# Shiftregisters.net
KiCad netlist of a schematic drawn in Altium Designer
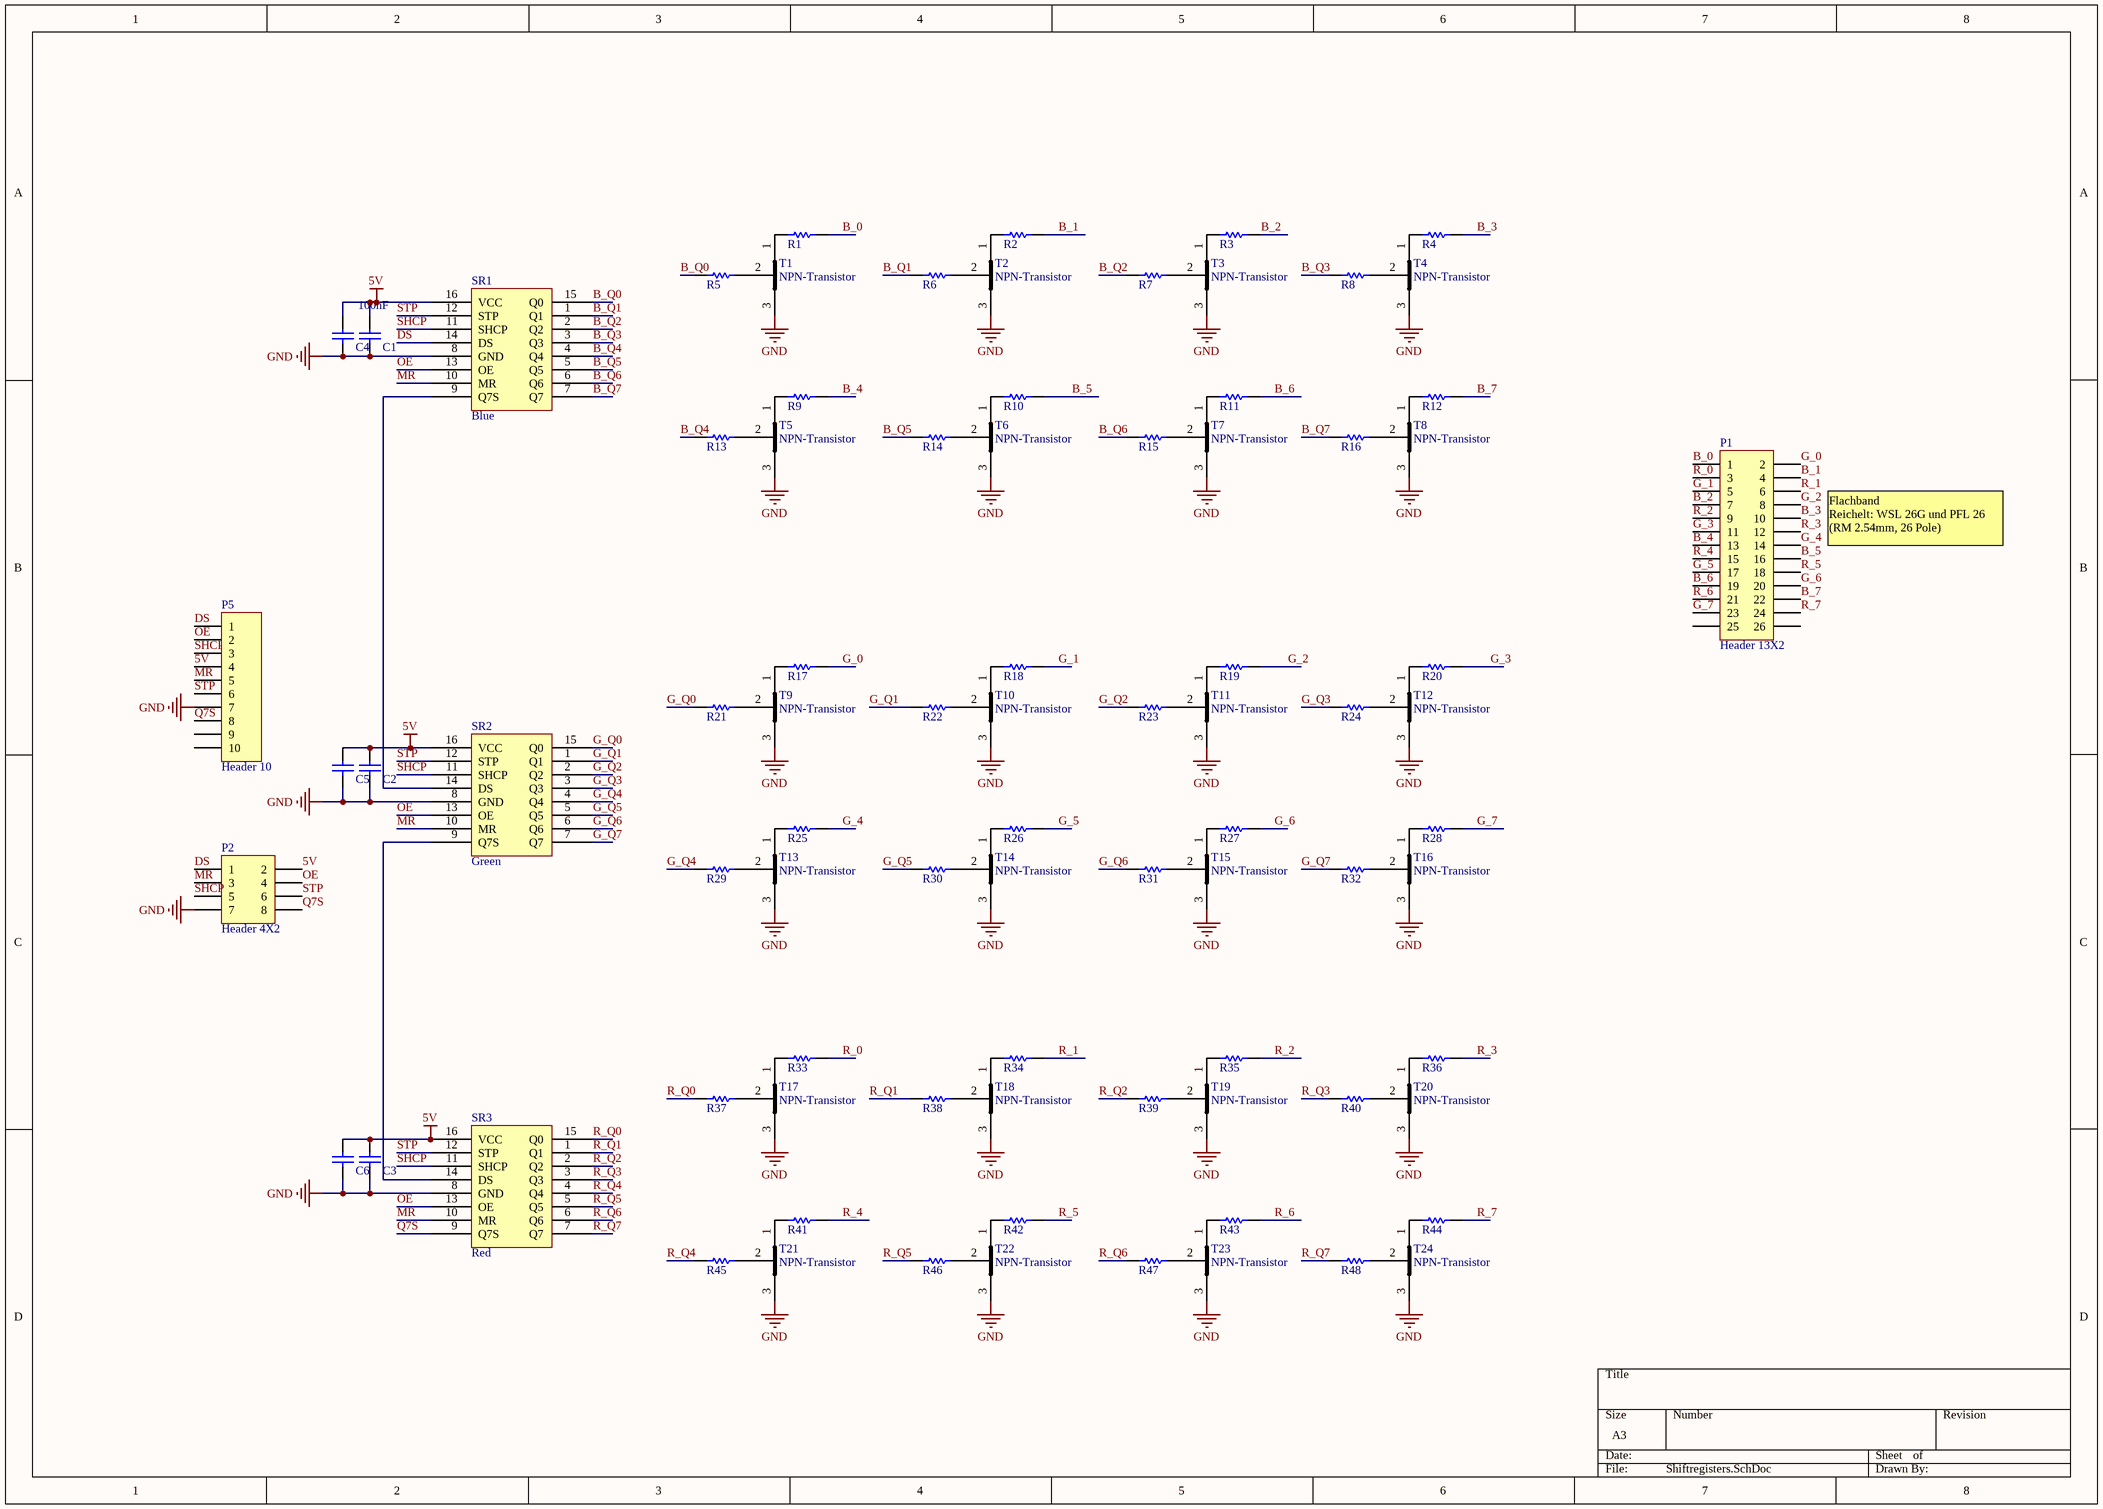
[diagram p0: Shiftregisters.SchDoc]

(export (version "E")
  (design (tool "Eeschema 10.0.6"))
  (components
    (comp (ref "C1")
      (value "100nF")
      (footprint "CAPC1206(3216)190_L")
      (description "CAP 100nF 16V Â±1% 1206 (3216 Metric) Thickness 1.9mm SMD")
      (fields (field (name "TOLERANCE") "Â±1%") (field (name "Comment") "CAP 100nF 16V 1206(3216)"))
      (libsource (lib "Altium Content Vault") (part "CMP-1037-04176-1"))
    )
    (comp (ref "C2")
      (value "CAP 100nF 16V 1206(3216)")
      (footprint "CAPC1206(3216)190_L")
      (description "CAP 100nF 16V Â±1% 1206 (3216 Metric) Thickness 1.9mm SMD")
      (fields (field (name "TOLERANCE") "Â±1%"))
      (libsource (lib "Altium Content Vault") (part "CAP"))
    )
    (comp (ref "C3")
      (value "CAP 100nF 16V 1206(3216)")
      (footprint "CAPC1206(3216)190_L")
      (description "CAP 100nF 16V Â±1% 1206 (3216 Metric) Thickness 1.9mm SMD")
      (fields (field (name "TOLERANCE") "Â±1%"))
      (libsource (lib "Altium Content Vault") (part "CAP"))
    )
    (comp (ref "C4")
      (value "CAP 1uF 16V 1206(3216)")
      (footprint "CAPC1206(3216)150_L")
      (description "CAP 1uF 16V Â±5% 1206 (3216 Metric) Thickness 1.45mm SMD")
      (fields (field (name "TOLERANCE") "Â±5%"))
      (libsource (lib "Altium Content Vault") (part "CAP"))
    )
    (comp (ref "C5")
      (value "CAP 1uF 16V 1206(3216)")
      (footprint "CAPC1206(3216)150_L")
      (description "CAP 1uF 16V Â±5% 1206 (3216 Metric) Thickness 1.45mm SMD")
      (fields (field (name "TOLERANCE") "Â±5%"))
      (libsource (lib "Altium Content Vault") (part "CAP"))
    )
    (comp (ref "C6")
      (value "CAP 1uF 16V 1206(3216)")
      (footprint "CAPC1206(3216)150_L")
      (description "CAP 1uF 16V Â±5% 1206 (3216 Metric) Thickness 1.45mm SMD")
      (fields (field (name "TOLERANCE") "Â±5%"))
      (libsource (lib "Altium Content Vault") (part "CAP"))
    )
    (comp (ref "P1")
      (value "Header 13X2")
      (footprint "HDR2X13")
      (description "Header, 13-Pin, Dual row")
      (fields (field (name "PUBLISHER") "Altium Limited"))
      (libsource (lib "Miscellaneous Connectors") (part "Header 13X2"))
    )
    (comp (ref "P2")
      (value "Header 4X2")
      (footprint "HDR2X4")
      (description "Header, 4-Pin, Dual row")
      (fields (field (name "PUBLISHER") "Altium Limited"))
      (libsource (lib "Miscellaneous Connectors") (part "Header 4X2"))
    )
    (comp (ref "P5")
      (value "Header 10")
      (footprint "10Pol Phoenix")
      (description "Header, 10-Pin")
      (fields (field (name "PUBLISHER") "Altium Limited"))
      (libsource (lib "Miscellaneous Connectors") (part "Header 10"))
    )
    (comp (ref "R1")
      (value "2R 5% 1206(3216)")
      (footprint "RESC1206(3216)_M")
      (description "2R 0.25W 5% 1206 (3216 Metric)  SMD")
      (fields (field (name "TOLERANCE") "5 %") (field (name "POWER") "0.25 W"))
      (libsource (lib "Altium Content Vault") (part "RES"))
    )
    (comp (ref "R2")
      (value "2R 5% 1206(3216)")
      (footprint "RESC1206(3216)_M")
      (description "2R 0.25W 5% 1206 (3216 Metric)  SMD")
      (fields (field (name "TOLERANCE") "5 %") (field (name "POWER") "0.25 W"))
      (libsource (lib "Altium Content Vault") (part "RES"))
    )
    (comp (ref "R3")
      (value "2R 5% 1206(3216)")
      (footprint "RESC1206(3216)_M")
      (description "2R 0.25W 5% 1206 (3216 Metric)  SMD")
      (fields (field (name "TOLERANCE") "5 %") (field (name "POWER") "0.25 W"))
      (libsource (lib "Altium Content Vault") (part "RES"))
    )
    (comp (ref "R4")
      (value "2R 5% 1206(3216)")
      (footprint "RESC1206(3216)_M")
      (description "2R 0.25W 5% 1206 (3216 Metric)  SMD")
      (fields (field (name "TOLERANCE") "5 %") (field (name "POWER") "0.25 W"))
      (libsource (lib "Altium Content Vault") (part "RES"))
    )
    (comp (ref "R5")
      (value "2R 5% 1206(3216)")
      (footprint "RESC1206(3216)_M")
      (description "2R 0.25W 5% 1206 (3216 Metric)  SMD")
      (fields (field (name "TOLERANCE") "5 %") (field (name "POWER") "0.25 W"))
      (libsource (lib "Altium Content Vault") (part "CMP-1014-00009-1"))
    )
    (comp (ref "R6")
      (value "2R 5% 1206(3216)")
      (footprint "RESC1206(3216)_M")
      (description "2R 0.25W 5% 1206 (3216 Metric)  SMD")
      (fields (field (name "TOLERANCE") "5 %") (field (name "POWER") "0.25 W"))
      (libsource (lib "Altium Content Vault") (part "RES"))
    )
    (comp (ref "R7")
      (value "2R 5% 1206(3216)")
      (footprint "RESC1206(3216)_M")
      (description "2R 0.25W 5% 1206 (3216 Metric)  SMD")
      (fields (field (name "TOLERANCE") "5 %") (field (name "POWER") "0.25 W"))
      (libsource (lib "Altium Content Vault") (part "RES"))
    )
    (comp (ref "R8")
      (value "2R 5% 1206(3216)")
      (footprint "RESC1206(3216)_M")
      (description "2R 0.25W 5% 1206 (3216 Metric)  SMD")
      (fields (field (name "TOLERANCE") "5 %") (field (name "POWER") "0.25 W"))
      (libsource (lib "Altium Content Vault") (part "RES"))
    )
    (comp (ref "R9")
      (value "2R 5% 1206(3216)")
      (footprint "RESC1206(3216)_M")
      (description "2R 0.25W 5% 1206 (3216 Metric)  SMD")
      (fields (field (name "TOLERANCE") "5 %") (field (name "POWER") "0.25 W"))
      (libsource (lib "Altium Content Vault") (part "RES"))
    )
    (comp (ref "R10")
      (value "2R 5% 1206(3216)")
      (footprint "RESC1206(3216)_M")
      (description "2R 0.25W 5% 1206 (3216 Metric)  SMD")
      (fields (field (name "TOLERANCE") "5 %") (field (name "POWER") "0.25 W"))
      (libsource (lib "Altium Content Vault") (part "RES"))
    )
    (comp (ref "R11")
      (value "2R 5% 1206(3216)")
      (footprint "RESC1206(3216)_M")
      (description "2R 0.25W 5% 1206 (3216 Metric)  SMD")
      (fields (field (name "TOLERANCE") "5 %") (field (name "POWER") "0.25 W"))
      (libsource (lib "Altium Content Vault") (part "RES"))
    )
    (comp (ref "R12")
      (value "2R 5% 1206(3216)")
      (footprint "RESC1206(3216)_M")
      (description "2R 0.25W 5% 1206 (3216 Metric)  SMD")
      (fields (field (name "TOLERANCE") "5 %") (field (name "POWER") "0.25 W"))
      (libsource (lib "Altium Content Vault") (part "RES"))
    )
    (comp (ref "R13")
      (value "2R 5% 1206(3216)")
      (footprint "RESC1206(3216)_M")
      (description "2R 0.25W 5% 1206 (3216 Metric)  SMD")
      (fields (field (name "TOLERANCE") "5 %") (field (name "POWER") "0.25 W"))
      (libsource (lib "Altium Content Vault") (part "RES"))
    )
    (comp (ref "R14")
      (value "2R 5% 1206(3216)")
      (footprint "RESC1206(3216)_M")
      (description "2R 0.25W 5% 1206 (3216 Metric)  SMD")
      (fields (field (name "TOLERANCE") "5 %") (field (name "POWER") "0.25 W"))
      (libsource (lib "Altium Content Vault") (part "RES"))
    )
    (comp (ref "R15")
      (value "2R 5% 1206(3216)")
      (footprint "RESC1206(3216)_M")
      (description "2R 0.25W 5% 1206 (3216 Metric)  SMD")
      (fields (field (name "TOLERANCE") "5 %") (field (name "POWER") "0.25 W"))
      (libsource (lib "Altium Content Vault") (part "RES"))
    )
    (comp (ref "R16")
      (value "2R 5% 1206(3216)")
      (footprint "RESC1206(3216)_M")
      (description "2R 0.25W 5% 1206 (3216 Metric)  SMD")
      (fields (field (name "TOLERANCE") "5 %") (field (name "POWER") "0.25 W"))
      (libsource (lib "Altium Content Vault") (part "RES"))
    )
    (comp (ref "R17")
      (value "2R 5% 1206(3216)")
      (footprint "RESC1206(3216)_M")
      (description "2R 0.25W 5% 1206 (3216 Metric)  SMD")
      (fields (field (name "TOLERANCE") "5 %") (field (name "POWER") "0.25 W"))
      (libsource (lib "Altium Content Vault") (part "RES"))
    )
    (comp (ref "R18")
      (value "2R 5% 1206(3216)")
      (footprint "RESC1206(3216)_M")
      (description "2R 0.25W 5% 1206 (3216 Metric)  SMD")
      (fields (field (name "TOLERANCE") "5 %") (field (name "POWER") "0.25 W"))
      (libsource (lib "Altium Content Vault") (part "RES"))
    )
    (comp (ref "R19")
      (value "2R 5% 1206(3216)")
      (footprint "RESC1206(3216)_M")
      (description "2R 0.25W 5% 1206 (3216 Metric)  SMD")
      (fields (field (name "TOLERANCE") "5 %") (field (name "POWER") "0.25 W"))
      (libsource (lib "Altium Content Vault") (part "RES"))
    )
    (comp (ref "R20")
      (value "2R 5% 1206(3216)")
      (footprint "RESC1206(3216)_M")
      (description "2R 0.25W 5% 1206 (3216 Metric)  SMD")
      (fields (field (name "TOLERANCE") "5 %") (field (name "POWER") "0.25 W"))
      (libsource (lib "Altium Content Vault") (part "RES"))
    )
    (comp (ref "R21")
      (value "2R 5% 1206(3216)")
      (footprint "RESC1206(3216)_M")
      (description "2R 0.25W 5% 1206 (3216 Metric)  SMD")
      (fields (field (name "TOLERANCE") "5 %") (field (name "POWER") "0.25 W"))
      (libsource (lib "Altium Content Vault") (part "RES"))
    )
    (comp (ref "R22")
      (value "2R 5% 1206(3216)")
      (footprint "RESC1206(3216)_M")
      (description "2R 0.25W 5% 1206 (3216 Metric)  SMD")
      (fields (field (name "TOLERANCE") "5 %") (field (name "POWER") "0.25 W"))
      (libsource (lib "Altium Content Vault") (part "RES"))
    )
    (comp (ref "R23")
      (value "2R 5% 1206(3216)")
      (footprint "RESC1206(3216)_M")
      (description "2R 0.25W 5% 1206 (3216 Metric)  SMD")
      (fields (field (name "TOLERANCE") "5 %") (field (name "POWER") "0.25 W"))
      (libsource (lib "Altium Content Vault") (part "RES"))
    )
    (comp (ref "R24")
      (value "2R 5% 1206(3216)")
      (footprint "RESC1206(3216)_M")
      (description "2R 0.25W 5% 1206 (3216 Metric)  SMD")
      (fields (field (name "TOLERANCE") "5 %") (field (name "POWER") "0.25 W"))
      (libsource (lib "Altium Content Vault") (part "RES"))
    )
    (comp (ref "R25")
      (value "2R 5% 1206(3216)")
      (footprint "RESC1206(3216)_M")
      (description "2R 0.25W 5% 1206 (3216 Metric)  SMD")
      (fields (field (name "TOLERANCE") "5 %") (field (name "POWER") "0.25 W"))
      (libsource (lib "Altium Content Vault") (part "RES"))
    )
    (comp (ref "R26")
      (value "2R 5% 1206(3216)")
      (footprint "RESC1206(3216)_M")
      (description "2R 0.25W 5% 1206 (3216 Metric)  SMD")
      (fields (field (name "TOLERANCE") "5 %") (field (name "POWER") "0.25 W"))
      (libsource (lib "Altium Content Vault") (part "RES"))
    )
    (comp (ref "R27")
      (value "2R 5% 1206(3216)")
      (footprint "RESC1206(3216)_M")
      (description "2R 0.25W 5% 1206 (3216 Metric)  SMD")
      (fields (field (name "TOLERANCE") "5 %") (field (name "POWER") "0.25 W"))
      (libsource (lib "Altium Content Vault") (part "RES"))
    )
    (comp (ref "R28")
      (value "2R 5% 1206(3216)")
      (footprint "RESC1206(3216)_M")
      (description "2R 0.25W 5% 1206 (3216 Metric)  SMD")
      (fields (field (name "TOLERANCE") "5 %") (field (name "POWER") "0.25 W"))
      (libsource (lib "Altium Content Vault") (part "RES"))
    )
    (comp (ref "R29")
      (value "2R 5% 1206(3216)")
      (footprint "RESC1206(3216)_M")
      (description "2R 0.25W 5% 1206 (3216 Metric)  SMD")
      (fields (field (name "TOLERANCE") "5 %") (field (name "POWER") "0.25 W"))
      (libsource (lib "Altium Content Vault") (part "RES"))
    )
    (comp (ref "R30")
      (value "2R 5% 1206(3216)")
      (footprint "RESC1206(3216)_M")
      (description "2R 0.25W 5% 1206 (3216 Metric)  SMD")
      (fields (field (name "TOLERANCE") "5 %") (field (name "POWER") "0.25 W"))
      (libsource (lib "Altium Content Vault") (part "RES"))
    )
    (comp (ref "R31")
      (value "2R 5% 1206(3216)")
      (footprint "RESC1206(3216)_M")
      (description "2R 0.25W 5% 1206 (3216 Metric)  SMD")
      (fields (field (name "TOLERANCE") "5 %") (field (name "POWER") "0.25 W"))
      (libsource (lib "Altium Content Vault") (part "RES"))
    )
    (comp (ref "R32")
      (value "2R 5% 1206(3216)")
      (footprint "RESC1206(3216)_M")
      (description "2R 0.25W 5% 1206 (3216 Metric)  SMD")
      (fields (field (name "TOLERANCE") "5 %") (field (name "POWER") "0.25 W"))
      (libsource (lib "Altium Content Vault") (part "RES"))
    )
    (comp (ref "R33")
      (value "2R 5% 1206(3216)")
      (footprint "RESC1206(3216)_M")
      (description "2R 0.25W 5% 1206 (3216 Metric)  SMD")
      (fields (field (name "TOLERANCE") "5 %") (field (name "POWER") "0.25 W"))
      (libsource (lib "Altium Content Vault") (part "RES"))
    )
    (comp (ref "R34")
      (value "2R 5% 1206(3216)")
      (footprint "RESC1206(3216)_M")
      (description "2R 0.25W 5% 1206 (3216 Metric)  SMD")
      (fields (field (name "TOLERANCE") "5 %") (field (name "POWER") "0.25 W"))
      (libsource (lib "Altium Content Vault") (part "RES"))
    )
    (comp (ref "R35")
      (value "2R 5% 1206(3216)")
      (footprint "RESC1206(3216)_M")
      (description "2R 0.25W 5% 1206 (3216 Metric)  SMD")
      (fields (field (name "TOLERANCE") "5 %") (field (name "POWER") "0.25 W"))
      (libsource (lib "Altium Content Vault") (part "RES"))
    )
    (comp (ref "R36")
      (value "2R 5% 1206(3216)")
      (footprint "RESC1206(3216)_M")
      (description "2R 0.25W 5% 1206 (3216 Metric)  SMD")
      (fields (field (name "TOLERANCE") "5 %") (field (name "POWER") "0.25 W"))
      (libsource (lib "Altium Content Vault") (part "RES"))
    )
    (comp (ref "R37")
      (value "2R 5% 1206(3216)")
      (footprint "RESC1206(3216)_M")
      (description "2R 0.25W 5% 1206 (3216 Metric)  SMD")
      (fields (field (name "TOLERANCE") "5 %") (field (name "POWER") "0.25 W"))
      (libsource (lib "Altium Content Vault") (part "RES"))
    )
    (comp (ref "R38")
      (value "2R 5% 1206(3216)")
      (footprint "RESC1206(3216)_M")
      (description "2R 0.25W 5% 1206 (3216 Metric)  SMD")
      (fields (field (name "TOLERANCE") "5 %") (field (name "POWER") "0.25 W"))
      (libsource (lib "Altium Content Vault") (part "RES"))
    )
    (comp (ref "R39")
      (value "2R 5% 1206(3216)")
      (footprint "RESC1206(3216)_M")
      (description "2R 0.25W 5% 1206 (3216 Metric)  SMD")
      (fields (field (name "TOLERANCE") "5 %") (field (name "POWER") "0.25 W"))
      (libsource (lib "Altium Content Vault") (part "RES"))
    )
    (comp (ref "R40")
      (value "2R 5% 1206(3216)")
      (footprint "RESC1206(3216)_M")
      (description "2R 0.25W 5% 1206 (3216 Metric)  SMD")
      (fields (field (name "TOLERANCE") "5 %") (field (name "POWER") "0.25 W"))
      (libsource (lib "Altium Content Vault") (part "RES"))
    )
    (comp (ref "R41")
      (value "2R 5% 1206(3216)")
      (footprint "RESC1206(3216)_M")
      (description "2R 0.25W 5% 1206 (3216 Metric)  SMD")
      (fields (field (name "TOLERANCE") "5 %") (field (name "POWER") "0.25 W"))
      (libsource (lib "Altium Content Vault") (part "RES"))
    )
    (comp (ref "R42")
      (value "2R 5% 1206(3216)")
      (footprint "RESC1206(3216)_M")
      (description "2R 0.25W 5% 1206 (3216 Metric)  SMD")
      (fields (field (name "TOLERANCE") "5 %") (field (name "POWER") "0.25 W"))
      (libsource (lib "Altium Content Vault") (part "RES"))
    )
    (comp (ref "R43")
      (value "2R 5% 1206(3216)")
      (footprint "RESC1206(3216)_M")
      (description "2R 0.25W 5% 1206 (3216 Metric)  SMD")
      (fields (field (name "TOLERANCE") "5 %") (field (name "POWER") "0.25 W"))
      (libsource (lib "Altium Content Vault") (part "RES"))
    )
    (comp (ref "R44")
      (value "2R 5% 1206(3216)")
      (footprint "RESC1206(3216)_M")
      (description "2R 0.25W 5% 1206 (3216 Metric)  SMD")
      (fields (field (name "TOLERANCE") "5 %") (field (name "POWER") "0.25 W"))
      (libsource (lib "Altium Content Vault") (part "RES"))
    )
    (comp (ref "R45")
      (value "2R 5% 1206(3216)")
      (footprint "RESC1206(3216)_M")
      (description "2R 0.25W 5% 1206 (3216 Metric)  SMD")
      (fields (field (name "TOLERANCE") "5 %") (field (name "POWER") "0.25 W"))
      (libsource (lib "Altium Content Vault") (part "CMP-1014-00009-1"))
    )
    (comp (ref "R46")
      (value "2R 5% 1206(3216)")
      (footprint "RESC1206(3216)_M")
      (description "2R 0.25W 5% 1206 (3216 Metric)  SMD")
      (fields (field (name "TOLERANCE") "5 %") (field (name "POWER") "0.25 W"))
      (libsource (lib "Altium Content Vault") (part "RES"))
    )
    (comp (ref "R47")
      (value "2R 5% 1206(3216)")
      (footprint "RESC1206(3216)_M")
      (description "2R 0.25W 5% 1206 (3216 Metric)  SMD")
      (fields (field (name "TOLERANCE") "5 %") (field (name "POWER") "0.25 W"))
      (libsource (lib "Altium Content Vault") (part "RES"))
    )
    (comp (ref "R48")
      (value "2R 5% 1206(3216)")
      (footprint "RESC1206(3216)_M")
      (description "2R 0.25W 5% 1206 (3216 Metric)  SMD")
      (fields (field (name "TOLERANCE") "5 %") (field (name "POWER") "0.25 W"))
      (libsource (lib "Altium Content Vault") (part "RES"))
    )
    (comp (ref "SR1")
      (value "Blue")
      (footprint "SOP16")
      (description "74HC595 Farnell:  2098004")
      (libsource (lib "RGB-Cube") (part "74HC595"))
    )
    (comp (ref "SR2")
      (value "Green")
      (footprint "SOP16")
      (description "74HC595 Farnell:  2098004")
      (libsource (lib "RGB-Cube") (part "74HC595"))
    )
    (comp (ref "SR3")
      (value "Red")
      (footprint "SOP16")
      (description "74HC595 Farnell:  2098004")
      (libsource (lib "RGB-Cube") (part "74HC595"))
    )
    (comp (ref "T1")
      (value "NPN-Transistor")
      (footprint "2N3904 - duplicate")
      (libsource (lib "RGB-Cube") (part "NPN-Transistor"))
    )
    (comp (ref "T2")
      (value "NPN-Transistor")
      (footprint "2N3904 - duplicate")
      (libsource (lib "RGB-Cube") (part "NPN-Transistor"))
    )
    (comp (ref "T3")
      (value "NPN-Transistor")
      (footprint "2N3904 - duplicate")
      (libsource (lib "RGB-Cube") (part "NPN-Transistor"))
    )
    (comp (ref "T4")
      (value "NPN-Transistor")
      (footprint "2N3904 - duplicate")
      (libsource (lib "RGB-Cube") (part "NPN-Transistor"))
    )
    (comp (ref "T5")
      (value "NPN-Transistor")
      (footprint "2N3904 - duplicate")
      (libsource (lib "RGB-Cube") (part "NPN-Transistor"))
    )
    (comp (ref "T6")
      (value "NPN-Transistor")
      (footprint "2N3904 - duplicate")
      (libsource (lib "RGB-Cube") (part "NPN-Transistor"))
    )
    (comp (ref "T7")
      (value "NPN-Transistor")
      (footprint "2N3904 - duplicate")
      (libsource (lib "RGB-Cube") (part "NPN-Transistor"))
    )
    (comp (ref "T8")
      (value "NPN-Transistor")
      (footprint "2N3904 - duplicate")
      (libsource (lib "RGB-Cube") (part "NPN-Transistor"))
    )
    (comp (ref "T9")
      (value "NPN-Transistor")
      (footprint "2N3904 - duplicate")
      (libsource (lib "RGB-Cube") (part "NPN-Transistor"))
    )
    (comp (ref "T10")
      (value "NPN-Transistor")
      (footprint "2N3904 - duplicate")
      (libsource (lib "RGB-Cube") (part "NPN-Transistor"))
    )
    (comp (ref "T11")
      (value "NPN-Transistor")
      (footprint "2N3904 - duplicate")
      (libsource (lib "RGB-Cube") (part "NPN-Transistor"))
    )
    (comp (ref "T12")
      (value "NPN-Transistor")
      (footprint "2N3904 - duplicate")
      (libsource (lib "RGB-Cube") (part "NPN-Transistor"))
    )
    (comp (ref "T13")
      (value "NPN-Transistor")
      (footprint "2N3904 - duplicate")
      (libsource (lib "RGB-Cube") (part "NPN-Transistor"))
    )
    (comp (ref "T14")
      (value "NPN-Transistor")
      (footprint "2N3904 - duplicate")
      (libsource (lib "RGB-Cube") (part "NPN-Transistor"))
    )
    (comp (ref "T15")
      (value "NPN-Transistor")
      (footprint "2N3904 - duplicate")
      (libsource (lib "RGB-Cube") (part "NPN-Transistor"))
    )
    (comp (ref "T16")
      (value "NPN-Transistor")
      (footprint "2N3904 - duplicate")
      (libsource (lib "RGB-Cube") (part "NPN-Transistor"))
    )
    (comp (ref "T17")
      (value "NPN-Transistor")
      (footprint "2N3904 - duplicate")
      (libsource (lib "RGB-Cube") (part "NPN-Transistor"))
    )
    (comp (ref "T18")
      (value "NPN-Transistor")
      (footprint "2N3904 - duplicate")
      (libsource (lib "RGB-Cube") (part "NPN-Transistor"))
    )
    (comp (ref "T19")
      (value "NPN-Transistor")
      (footprint "2N3904 - duplicate")
      (libsource (lib "RGB-Cube") (part "NPN-Transistor"))
    )
    (comp (ref "T20")
      (value "NPN-Transistor")
      (footprint "2N3904 - duplicate")
      (libsource (lib "RGB-Cube") (part "NPN-Transistor"))
    )
    (comp (ref "T21")
      (value "NPN-Transistor")
      (footprint "2N3904 - duplicate")
      (libsource (lib "RGB-Cube") (part "NPN-Transistor"))
    )
    (comp (ref "T22")
      (value "NPN-Transistor")
      (footprint "2N3904 - duplicate")
      (libsource (lib "RGB-Cube") (part "NPN-Transistor"))
    )
    (comp (ref "T23")
      (value "NPN-Transistor")
      (footprint "2N3904 - duplicate")
      (libsource (lib "RGB-Cube") (part "NPN-Transistor"))
    )
    (comp (ref "T24")
      (value "NPN-Transistor")
      (footprint "2N3904 - duplicate")
      (libsource (lib "RGB-Cube") (part "NPN-Transistor"))
    )
  )
  (nets
    (net (code "1") (name "/B_0") (class "Default")
      (node (ref "P1") (pin "1") (pinfunction "1_1") (pintype "passive"))
      (node (ref "R1") (pin "1") (pinfunction "1_1") (pintype "passive"))
    )
    (net (code "2") (name "/B_1") (class "Default")
      (node (ref "P1") (pin "4") (pinfunction "4_4") (pintype "passive"))
      (node (ref "R2") (pin "1") (pinfunction "1_1") (pintype "passive"))
    )
    (net (code "3") (name "/B_2") (class "Default")
      (node (ref "P1") (pin "7") (pinfunction "7_7") (pintype "passive"))
      (node (ref "R3") (pin "1") (pinfunction "1_1") (pintype "passive"))
    )
    (net (code "4") (name "/B_3") (class "Default")
      (node (ref "P1") (pin "10") (pinfunction "10_10") (pintype "passive"))
      (node (ref "R4") (pin "1") (pinfunction "1_1") (pintype "passive"))
    )
    (net (code "5") (name "/B_4") (class "Default")
      (node (ref "P1") (pin "13") (pinfunction "13_13") (pintype "passive"))
      (node (ref "R9") (pin "1") (pinfunction "1_1") (pintype "passive"))
    )
    (net (code "6") (name "/B_5") (class "Default")
      (node (ref "P1") (pin "16") (pinfunction "16_16") (pintype "passive"))
      (node (ref "R10") (pin "1") (pinfunction "1_1") (pintype "passive"))
    )
    (net (code "7") (name "/B_6") (class "Default")
      (node (ref "P1") (pin "19") (pinfunction "19_19") (pintype "passive"))
      (node (ref "R11") (pin "1") (pinfunction "1_1") (pintype "passive"))
    )
    (net (code "8") (name "/B_7") (class "Default")
      (node (ref "P1") (pin "22") (pinfunction "22_22") (pintype "passive"))
      (node (ref "R12") (pin "1") (pinfunction "1_1") (pintype "passive"))
    )
    (net (code "9") (name "/B_Q0") (class "Default")
      (node (ref "R5") (pin "1") (pinfunction "1_1") (pintype "passive"))
      (node (ref "SR1") (pin "15") (pinfunction "Q0_15") (pintype "passive"))
    )
    (net (code "10") (name "/B_Q1") (class "Default")
      (node (ref "R6") (pin "1") (pinfunction "1_1") (pintype "passive"))
      (node (ref "SR1") (pin "1") (pinfunction "Q1_1") (pintype "passive"))
    )
    (net (code "11") (name "/B_Q2") (class "Default")
      (node (ref "R7") (pin "1") (pinfunction "1_1") (pintype "passive"))
      (node (ref "SR1") (pin "2") (pinfunction "Q2_2") (pintype "passive"))
    )
    (net (code "12") (name "/B_Q3") (class "Default")
      (node (ref "R8") (pin "1") (pinfunction "1_1") (pintype "passive"))
      (node (ref "SR1") (pin "3") (pinfunction "Q3_3") (pintype "passive"))
    )
    (net (code "13") (name "/B_Q4") (class "Default")
      (node (ref "R13") (pin "1") (pinfunction "1_1") (pintype "passive"))
      (node (ref "SR1") (pin "4") (pinfunction "Q4_4") (pintype "passive"))
    )
    (net (code "14") (name "/B_Q5") (class "Default")
      (node (ref "R14") (pin "1") (pinfunction "1_1") (pintype "passive"))
      (node (ref "SR1") (pin "5") (pinfunction "Q5_5") (pintype "passive"))
    )
    (net (code "15") (name "/B_Q6") (class "Default")
      (node (ref "R15") (pin "1") (pinfunction "1_1") (pintype "passive"))
      (node (ref "SR1") (pin "6") (pinfunction "Q6_6") (pintype "passive"))
    )
    (net (code "16") (name "/B_Q7") (class "Default")
      (node (ref "R16") (pin "1") (pinfunction "1_1") (pintype "passive"))
      (node (ref "SR1") (pin "7") (pinfunction "Q7_7") (pintype "passive"))
    )
    (net (code "17") (name "/DS") (class "Default")
      (node (ref "P2") (pin "1") (pinfunction "1_1") (pintype "passive"))
      (node (ref "P5") (pin "1") (pinfunction "1_1") (pintype "passive"))
      (node (ref "SR1") (pin "14") (pinfunction "DS_14") (pintype "passive"))
    )
    (net (code "18") (name "/G_0") (class "Default")
      (node (ref "P1") (pin "2") (pinfunction "2_2") (pintype "passive"))
      (node (ref "R17") (pin "1") (pinfunction "1_1") (pintype "passive"))
    )
    (net (code "19") (name "/G_1") (class "Default")
      (node (ref "P1") (pin "5") (pinfunction "5_5") (pintype "passive"))
      (node (ref "R18") (pin "1") (pinfunction "1_1") (pintype "passive"))
    )
    (net (code "20") (name "/G_2") (class "Default")
      (node (ref "P1") (pin "8") (pinfunction "8_8") (pintype "passive"))
      (node (ref "R19") (pin "1") (pinfunction "1_1") (pintype "passive"))
    )
    (net (code "21") (name "/G_3") (class "Default")
      (node (ref "P1") (pin "11") (pinfunction "11_11") (pintype "passive"))
      (node (ref "R20") (pin "1") (pinfunction "1_1") (pintype "passive"))
    )
    (net (code "22") (name "/G_4") (class "Default")
      (node (ref "P1") (pin "14") (pinfunction "14_14") (pintype "passive"))
      (node (ref "R25") (pin "1") (pinfunction "1_1") (pintype "passive"))
    )
    (net (code "23") (name "/G_5") (class "Default")
      (node (ref "P1") (pin "17") (pinfunction "17_17") (pintype "passive"))
      (node (ref "R26") (pin "1") (pinfunction "1_1") (pintype "passive"))
    )
    (net (code "24") (name "/G_6") (class "Default")
      (node (ref "P1") (pin "20") (pinfunction "20_20") (pintype "passive"))
      (node (ref "R27") (pin "1") (pinfunction "1_1") (pintype "passive"))
    )
    (net (code "25") (name "/G_7") (class "Default")
      (node (ref "P1") (pin "23") (pinfunction "23_23") (pintype "passive"))
      (node (ref "R28") (pin "1") (pinfunction "1_1") (pintype "passive"))
    )
    (net (code "26") (name "/G_Q0") (class "Default")
      (node (ref "R21") (pin "1") (pinfunction "1_1") (pintype "passive"))
      (node (ref "SR2") (pin "15") (pinfunction "Q0_15") (pintype "passive"))
    )
    (net (code "27") (name "/G_Q1") (class "Default")
      (node (ref "R22") (pin "1") (pinfunction "1_1") (pintype "passive"))
      (node (ref "SR2") (pin "1") (pinfunction "Q1_1") (pintype "passive"))
    )
    (net (code "28") (name "/G_Q2") (class "Default")
      (node (ref "R23") (pin "1") (pinfunction "1_1") (pintype "passive"))
      (node (ref "SR2") (pin "2") (pinfunction "Q2_2") (pintype "passive"))
    )
    (net (code "29") (name "/G_Q3") (class "Default")
      (node (ref "R24") (pin "1") (pinfunction "1_1") (pintype "passive"))
      (node (ref "SR2") (pin "3") (pinfunction "Q3_3") (pintype "passive"))
    )
    (net (code "30") (name "/G_Q4") (class "Default")
      (node (ref "R29") (pin "1") (pinfunction "1_1") (pintype "passive"))
      (node (ref "SR2") (pin "4") (pinfunction "Q4_4") (pintype "passive"))
    )
    (net (code "31") (name "/G_Q5") (class "Default")
      (node (ref "R30") (pin "1") (pinfunction "1_1") (pintype "passive"))
      (node (ref "SR2") (pin "5") (pinfunction "Q5_5") (pintype "passive"))
    )
    (net (code "32") (name "/G_Q6") (class "Default")
      (node (ref "R31") (pin "1") (pinfunction "1_1") (pintype "passive"))
      (node (ref "SR2") (pin "6") (pinfunction "Q6_6") (pintype "passive"))
    )
    (net (code "33") (name "/G_Q7") (class "Default")
      (node (ref "R32") (pin "1") (pinfunction "1_1") (pintype "passive"))
      (node (ref "SR2") (pin "7") (pinfunction "Q7_7") (pintype "passive"))
    )
    (net (code "34") (name "/MR") (class "Default")
      (node (ref "P2") (pin "3") (pinfunction "3_3") (pintype "passive"))
      (node (ref "P5") (pin "5") (pinfunction "5_5") (pintype "passive"))
      (node (ref "SR1") (pin "10") (pinfunction "MR_10") (pintype "passive"))
      (node (ref "SR2") (pin "10") (pinfunction "MR_10") (pintype "passive"))
      (node (ref "SR3") (pin "10") (pinfunction "MR_10") (pintype "passive"))
    )
    (net (code "35") (name "/OE") (class "Default")
      (node (ref "P2") (pin "4") (pinfunction "4_4") (pintype "passive"))
      (node (ref "P5") (pin "2") (pinfunction "2_2") (pintype "passive"))
      (node (ref "SR1") (pin "13") (pinfunction "OE_13") (pintype "passive"))
      (node (ref "SR2") (pin "13") (pinfunction "OE_13") (pintype "passive"))
      (node (ref "SR3") (pin "13") (pinfunction "OE_13") (pintype "passive"))
    )
    (net (code "36") (name "/Q7S") (class "Default")
      (node (ref "P2") (pin "8") (pinfunction "8_8") (pintype "passive"))
      (node (ref "P5") (pin "8") (pinfunction "8_8") (pintype "passive"))
      (node (ref "SR3") (pin "9") (pinfunction "Q7S_9") (pintype "passive"))
    )
    (net (code "37") (name "/R_0") (class "Default")
      (node (ref "P1") (pin "3") (pinfunction "3_3") (pintype "passive"))
      (node (ref "R33") (pin "1") (pinfunction "1_1") (pintype "passive"))
    )
    (net (code "38") (name "/R_1") (class "Default")
      (node (ref "P1") (pin "6") (pinfunction "6_6") (pintype "passive"))
      (node (ref "R34") (pin "1") (pinfunction "1_1") (pintype "passive"))
    )
    (net (code "39") (name "/R_2") (class "Default")
      (node (ref "P1") (pin "9") (pinfunction "9_9") (pintype "passive"))
      (node (ref "R35") (pin "1") (pinfunction "1_1") (pintype "passive"))
    )
    (net (code "40") (name "/R_3") (class "Default")
      (node (ref "P1") (pin "12") (pinfunction "12_12") (pintype "passive"))
      (node (ref "R36") (pin "1") (pinfunction "1_1") (pintype "passive"))
    )
    (net (code "41") (name "/R_4") (class "Default")
      (node (ref "P1") (pin "15") (pinfunction "15_15") (pintype "passive"))
      (node (ref "R41") (pin "1") (pinfunction "1_1") (pintype "passive"))
    )
    (net (code "42") (name "/R_5") (class "Default")
      (node (ref "P1") (pin "18") (pinfunction "18_18") (pintype "passive"))
      (node (ref "R42") (pin "1") (pinfunction "1_1") (pintype "passive"))
    )
    (net (code "43") (name "/R_6") (class "Default")
      (node (ref "P1") (pin "21") (pinfunction "21_21") (pintype "passive"))
      (node (ref "R43") (pin "1") (pinfunction "1_1") (pintype "passive"))
    )
    (net (code "44") (name "/R_7") (class "Default")
      (node (ref "P1") (pin "24") (pinfunction "24_24") (pintype "passive"))
      (node (ref "R44") (pin "1") (pinfunction "1_1") (pintype "passive"))
    )
    (net (code "45") (name "/R_Q0") (class "Default")
      (node (ref "R37") (pin "1") (pinfunction "1_1") (pintype "passive"))
      (node (ref "SR3") (pin "15") (pinfunction "Q0_15") (pintype "passive"))
    )
    (net (code "46") (name "/R_Q1") (class "Default")
      (node (ref "R38") (pin "1") (pinfunction "1_1") (pintype "passive"))
      (node (ref "SR3") (pin "1") (pinfunction "Q1_1") (pintype "passive"))
    )
    (net (code "47") (name "/R_Q2") (class "Default")
      (node (ref "R39") (pin "1") (pinfunction "1_1") (pintype "passive"))
      (node (ref "SR3") (pin "2") (pinfunction "Q2_2") (pintype "passive"))
    )
    (net (code "48") (name "/R_Q3") (class "Default")
      (node (ref "R40") (pin "1") (pinfunction "1_1") (pintype "passive"))
      (node (ref "SR3") (pin "3") (pinfunction "Q3_3") (pintype "passive"))
    )
    (net (code "49") (name "/R_Q4") (class "Default")
      (node (ref "R45") (pin "1") (pinfunction "1_1") (pintype "passive"))
      (node (ref "SR3") (pin "4") (pinfunction "Q4_4") (pintype "passive"))
    )
    (net (code "50") (name "/R_Q5") (class "Default")
      (node (ref "R46") (pin "1") (pinfunction "1_1") (pintype "passive"))
      (node (ref "SR3") (pin "5") (pinfunction "Q5_5") (pintype "passive"))
    )
    (net (code "51") (name "/R_Q6") (class "Default")
      (node (ref "R47") (pin "1") (pinfunction "1_1") (pintype "passive"))
      (node (ref "SR3") (pin "6") (pinfunction "Q6_6") (pintype "passive"))
    )
    (net (code "52") (name "/R_Q7") (class "Default")
      (node (ref "R48") (pin "1") (pinfunction "1_1") (pintype "passive"))
      (node (ref "SR3") (pin "7") (pinfunction "Q7_7") (pintype "passive"))
    )
    (net (code "53") (name "/SHCP") (class "Default")
      (node (ref "P2") (pin "5") (pinfunction "5_5") (pintype "passive"))
      (node (ref "P5") (pin "3") (pinfunction "3_3") (pintype "passive"))
      (node (ref "SR1") (pin "11") (pinfunction "SHCP_11") (pintype "passive"))
      (node (ref "SR2") (pin "11") (pinfunction "SHCP_11") (pintype "passive"))
      (node (ref "SR3") (pin "11") (pinfunction "SHCP_11") (pintype "passive"))
    )
    (net (code "54") (name "/STP") (class "Default")
      (node (ref "P2") (pin "6") (pinfunction "6_6") (pintype "passive"))
      (node (ref "P5") (pin "6") (pinfunction "6_6") (pintype "passive"))
      (node (ref "SR1") (pin "12") (pinfunction "STP_12") (pintype "passive"))
      (node (ref "SR2") (pin "12") (pinfunction "STP_12") (pintype "passive"))
      (node (ref "SR3") (pin "12") (pinfunction "STP_12") (pintype "passive"))
    )
    (net (code "55") (name "5V") (class "Default")
      (node (ref "C1") (pin "2") (pinfunction "2_2") (pintype "passive"))
      (node (ref "C2") (pin "1") (pinfunction "1_1") (pintype "passive"))
      (node (ref "C3") (pin "2") (pinfunction "2_2") (pintype "passive"))
      (node (ref "C4") (pin "2") (pinfunction "2_2") (pintype "passive"))
      (node (ref "C5") (pin "2") (pinfunction "2_2") (pintype "passive"))
      (node (ref "C6") (pin "2") (pinfunction "2_2") (pintype "passive"))
      (node (ref "P2") (pin "2") (pinfunction "2_2") (pintype "passive"))
      (node (ref "P5") (pin "4") (pinfunction "4_4") (pintype "passive"))
      (node (ref "SR1") (pin "16") (pinfunction "VCC_16") (pintype "passive"))
      (node (ref "SR2") (pin "16") (pinfunction "VCC_16") (pintype "passive"))
      (node (ref "SR3") (pin "16") (pinfunction "VCC_16") (pintype "passive"))
    )
    (net (code "56") (name "GND") (class "Default")
      (node (ref "C1") (pin "1") (pinfunction "1_1") (pintype "passive"))
      (node (ref "C2") (pin "2") (pinfunction "2_2") (pintype "passive"))
      (node (ref "C3") (pin "1") (pinfunction "1_1") (pintype "passive"))
      (node (ref "C4") (pin "1") (pinfunction "1_1") (pintype "passive"))
      (node (ref "C5") (pin "1") (pinfunction "1_1") (pintype "passive"))
      (node (ref "C6") (pin "1") (pinfunction "1_1") (pintype "passive"))
      (node (ref "P2") (pin "7") (pinfunction "7_7") (pintype "passive"))
      (node (ref "P5") (pin "7") (pinfunction "7_7") (pintype "passive"))
      (node (ref "SR1") (pin "8") (pinfunction "GND_8") (pintype "passive"))
      (node (ref "SR2") (pin "8") (pinfunction "GND_8") (pintype "passive"))
      (node (ref "SR3") (pin "8") (pinfunction "GND_8") (pintype "passive"))
      (node (ref "T1") (pin "3") (pintype "passive"))
      (node (ref "T10") (pin "3") (pintype "passive"))
      (node (ref "T11") (pin "3") (pintype "passive"))
      (node (ref "T12") (pin "3") (pintype "passive"))
      (node (ref "T13") (pin "3") (pintype "passive"))
      (node (ref "T14") (pin "3") (pintype "passive"))
      (node (ref "T15") (pin "3") (pintype "passive"))
      (node (ref "T16") (pin "3") (pintype "passive"))
      (node (ref "T17") (pin "3") (pintype "passive"))
      (node (ref "T18") (pin "3") (pintype "passive"))
      (node (ref "T19") (pin "3") (pintype "passive"))
      (node (ref "T2") (pin "3") (pintype "passive"))
      (node (ref "T20") (pin "3") (pintype "passive"))
      (node (ref "T21") (pin "3") (pintype "passive"))
      (node (ref "T22") (pin "3") (pintype "passive"))
      (node (ref "T23") (pin "3") (pintype "passive"))
      (node (ref "T24") (pin "3") (pintype "passive"))
      (node (ref "T3") (pin "3") (pintype "passive"))
      (node (ref "T4") (pin "3") (pintype "passive"))
      (node (ref "T5") (pin "3") (pintype "passive"))
      (node (ref "T6") (pin "3") (pintype "passive"))
      (node (ref "T7") (pin "3") (pintype "passive"))
      (node (ref "T8") (pin "3") (pintype "passive"))
      (node (ref "T9") (pin "3") (pintype "passive"))
    )
    (net (code "57") (name "Net-(R1-Pad2)") (class "Default")
      (node (ref "R1") (pin "2") (pinfunction "2_2") (pintype "passive"))
      (node (ref "T1") (pin "1") (pintype "passive"))
    )
    (net (code "58") (name "Net-(R2-Pad2)") (class "Default")
      (node (ref "R2") (pin "2") (pinfunction "2_2") (pintype "passive"))
      (node (ref "T2") (pin "1") (pintype "passive"))
    )
    (net (code "59") (name "Net-(R3-Pad2)") (class "Default")
      (node (ref "R3") (pin "2") (pinfunction "2_2") (pintype "passive"))
      (node (ref "T3") (pin "1") (pintype "passive"))
    )
    (net (code "60") (name "Net-(R4-Pad2)") (class "Default")
      (node (ref "R4") (pin "2") (pinfunction "2_2") (pintype "passive"))
      (node (ref "T4") (pin "1") (pintype "passive"))
    )
    (net (code "61") (name "Net-(R5-Pad2)") (class "Default")
      (node (ref "R5") (pin "2") (pinfunction "2_2") (pintype "passive"))
      (node (ref "T1") (pin "2") (pintype "passive"))
    )
    (net (code "62") (name "Net-(R6-Pad2)") (class "Default")
      (node (ref "R6") (pin "2") (pinfunction "2_2") (pintype "passive"))
      (node (ref "T2") (pin "2") (pintype "passive"))
    )
    (net (code "63") (name "Net-(R7-Pad2)") (class "Default")
      (node (ref "R7") (pin "2") (pinfunction "2_2") (pintype "passive"))
      (node (ref "T3") (pin "2") (pintype "passive"))
    )
    (net (code "64") (name "Net-(R8-Pad2)") (class "Default")
      (node (ref "R8") (pin "2") (pinfunction "2_2") (pintype "passive"))
      (node (ref "T4") (pin "2") (pintype "passive"))
    )
    (net (code "65") (name "Net-(R9-Pad2)") (class "Default")
      (node (ref "R9") (pin "2") (pinfunction "2_2") (pintype "passive"))
      (node (ref "T5") (pin "1") (pintype "passive"))
    )
    (net (code "66") (name "Net-(R10-Pad2)") (class "Default")
      (node (ref "R10") (pin "2") (pinfunction "2_2") (pintype "passive"))
      (node (ref "T6") (pin "1") (pintype "passive"))
    )
    (net (code "67") (name "Net-(R11-Pad2)") (class "Default")
      (node (ref "R11") (pin "2") (pinfunction "2_2") (pintype "passive"))
      (node (ref "T7") (pin "1") (pintype "passive"))
    )
    (net (code "68") (name "Net-(R12-Pad2)") (class "Default")
      (node (ref "R12") (pin "2") (pinfunction "2_2") (pintype "passive"))
      (node (ref "T8") (pin "1") (pintype "passive"))
    )
    (net (code "69") (name "Net-(R13-Pad2)") (class "Default")
      (node (ref "R13") (pin "2") (pinfunction "2_2") (pintype "passive"))
      (node (ref "T5") (pin "2") (pintype "passive"))
    )
    (net (code "70") (name "Net-(R14-Pad2)") (class "Default")
      (node (ref "R14") (pin "2") (pinfunction "2_2") (pintype "passive"))
      (node (ref "T6") (pin "2") (pintype "passive"))
    )
    (net (code "71") (name "Net-(R15-Pad2)") (class "Default")
      (node (ref "R15") (pin "2") (pinfunction "2_2") (pintype "passive"))
      (node (ref "T7") (pin "2") (pintype "passive"))
    )
    (net (code "72") (name "Net-(R16-Pad2)") (class "Default")
      (node (ref "R16") (pin "2") (pinfunction "2_2") (pintype "passive"))
      (node (ref "T8") (pin "2") (pintype "passive"))
    )
    (net (code "73") (name "Net-(R17-Pad2)") (class "Default")
      (node (ref "R17") (pin "2") (pinfunction "2_2") (pintype "passive"))
      (node (ref "T9") (pin "1") (pintype "passive"))
    )
    (net (code "74") (name "Net-(R18-Pad2)") (class "Default")
      (node (ref "R18") (pin "2") (pinfunction "2_2") (pintype "passive"))
      (node (ref "T10") (pin "1") (pintype "passive"))
    )
    (net (code "75") (name "Net-(R19-Pad2)") (class "Default")
      (node (ref "R19") (pin "2") (pinfunction "2_2") (pintype "passive"))
      (node (ref "T11") (pin "1") (pintype "passive"))
    )
    (net (code "76") (name "Net-(R20-Pad2)") (class "Default")
      (node (ref "R20") (pin "2") (pinfunction "2_2") (pintype "passive"))
      (node (ref "T12") (pin "1") (pintype "passive"))
    )
    (net (code "77") (name "Net-(R21-Pad2)") (class "Default")
      (node (ref "R21") (pin "2") (pinfunction "2_2") (pintype "passive"))
      (node (ref "T9") (pin "2") (pintype "passive"))
    )
    (net (code "78") (name "Net-(R22-Pad2)") (class "Default")
      (node (ref "R22") (pin "2") (pinfunction "2_2") (pintype "passive"))
      (node (ref "T10") (pin "2") (pintype "passive"))
    )
    (net (code "79") (name "Net-(R23-Pad2)") (class "Default")
      (node (ref "R23") (pin "2") (pinfunction "2_2") (pintype "passive"))
      (node (ref "T11") (pin "2") (pintype "passive"))
    )
    (net (code "80") (name "Net-(R24-Pad2)") (class "Default")
      (node (ref "R24") (pin "2") (pinfunction "2_2") (pintype "passive"))
      (node (ref "T12") (pin "2") (pintype "passive"))
    )
    (net (code "81") (name "Net-(R25-Pad2)") (class "Default")
      (node (ref "R25") (pin "2") (pinfunction "2_2") (pintype "passive"))
      (node (ref "T13") (pin "1") (pintype "passive"))
    )
    (net (code "82") (name "Net-(R26-Pad2)") (class "Default")
      (node (ref "R26") (pin "2") (pinfunction "2_2") (pintype "passive"))
      (node (ref "T14") (pin "1") (pintype "passive"))
    )
    (net (code "83") (name "Net-(R27-Pad2)") (class "Default")
      (node (ref "R27") (pin "2") (pinfunction "2_2") (pintype "passive"))
      (node (ref "T15") (pin "1") (pintype "passive"))
    )
    (net (code "84") (name "Net-(R28-Pad2)") (class "Default")
      (node (ref "R28") (pin "2") (pinfunction "2_2") (pintype "passive"))
      (node (ref "T16") (pin "1") (pintype "passive"))
    )
    (net (code "85") (name "Net-(R29-Pad2)") (class "Default")
      (node (ref "R29") (pin "2") (pinfunction "2_2") (pintype "passive"))
      (node (ref "T13") (pin "2") (pintype "passive"))
    )
    (net (code "86") (name "Net-(R30-Pad2)") (class "Default")
      (node (ref "R30") (pin "2") (pinfunction "2_2") (pintype "passive"))
      (node (ref "T14") (pin "2") (pintype "passive"))
    )
    (net (code "87") (name "Net-(R31-Pad2)") (class "Default")
      (node (ref "R31") (pin "2") (pinfunction "2_2") (pintype "passive"))
      (node (ref "T15") (pin "2") (pintype "passive"))
    )
    (net (code "88") (name "Net-(R32-Pad2)") (class "Default")
      (node (ref "R32") (pin "2") (pinfunction "2_2") (pintype "passive"))
      (node (ref "T16") (pin "2") (pintype "passive"))
    )
    (net (code "89") (name "Net-(R33-Pad2)") (class "Default")
      (node (ref "R33") (pin "2") (pinfunction "2_2") (pintype "passive"))
      (node (ref "T17") (pin "1") (pintype "passive"))
    )
    (net (code "90") (name "Net-(R34-Pad2)") (class "Default")
      (node (ref "R34") (pin "2") (pinfunction "2_2") (pintype "passive"))
      (node (ref "T18") (pin "1") (pintype "passive"))
    )
    (net (code "91") (name "Net-(R35-Pad2)") (class "Default")
      (node (ref "R35") (pin "2") (pinfunction "2_2") (pintype "passive"))
      (node (ref "T19") (pin "1") (pintype "passive"))
    )
    (net (code "92") (name "Net-(R36-Pad2)") (class "Default")
      (node (ref "R36") (pin "2") (pinfunction "2_2") (pintype "passive"))
      (node (ref "T20") (pin "1") (pintype "passive"))
    )
    (net (code "93") (name "Net-(R37-Pad2)") (class "Default")
      (node (ref "R37") (pin "2") (pinfunction "2_2") (pintype "passive"))
      (node (ref "T17") (pin "2") (pintype "passive"))
    )
    (net (code "94") (name "Net-(R38-Pad2)") (class "Default")
      (node (ref "R38") (pin "2") (pinfunction "2_2") (pintype "passive"))
      (node (ref "T18") (pin "2") (pintype "passive"))
    )
    (net (code "95") (name "Net-(R39-Pad2)") (class "Default")
      (node (ref "R39") (pin "2") (pinfunction "2_2") (pintype "passive"))
      (node (ref "T19") (pin "2") (pintype "passive"))
    )
    (net (code "96") (name "Net-(R40-Pad2)") (class "Default")
      (node (ref "R40") (pin "2") (pinfunction "2_2") (pintype "passive"))
      (node (ref "T20") (pin "2") (pintype "passive"))
    )
    (net (code "97") (name "Net-(R41-Pad2)") (class "Default")
      (node (ref "R41") (pin "2") (pinfunction "2_2") (pintype "passive"))
      (node (ref "T21") (pin "1") (pintype "passive"))
    )
    (net (code "98") (name "Net-(R42-Pad2)") (class "Default")
      (node (ref "R42") (pin "2") (pinfunction "2_2") (pintype "passive"))
      (node (ref "T22") (pin "1") (pintype "passive"))
    )
    (net (code "99") (name "Net-(R43-Pad2)") (class "Default")
      (node (ref "R43") (pin "2") (pinfunction "2_2") (pintype "passive"))
      (node (ref "T23") (pin "1") (pintype "passive"))
    )
    (net (code "100") (name "Net-(R44-Pad2)") (class "Default")
      (node (ref "R44") (pin "2") (pinfunction "2_2") (pintype "passive"))
      (node (ref "T24") (pin "1") (pintype "passive"))
    )
    (net (code "101") (name "Net-(R45-Pad2)") (class "Default")
      (node (ref "R45") (pin "2") (pinfunction "2_2") (pintype "passive"))
      (node (ref "T21") (pin "2") (pintype "passive"))
    )
    (net (code "102") (name "Net-(R46-Pad2)") (class "Default")
      (node (ref "R46") (pin "2") (pinfunction "2_2") (pintype "passive"))
      (node (ref "T22") (pin "2") (pintype "passive"))
    )
    (net (code "103") (name "Net-(R47-Pad2)") (class "Default")
      (node (ref "R47") (pin "2") (pinfunction "2_2") (pintype "passive"))
      (node (ref "T23") (pin "2") (pintype "passive"))
    )
    (net (code "104") (name "Net-(R48-Pad2)") (class "Default")
      (node (ref "R48") (pin "2") (pinfunction "2_2") (pintype "passive"))
      (node (ref "T24") (pin "2") (pintype "passive"))
    )
    (net (code "105") (name "Net-(SR1-Q7S)") (class "Default")
      (node (ref "SR1") (pin "9") (pinfunction "Q7S_9") (pintype "passive"))
      (node (ref "SR2") (pin "14") (pinfunction "DS_14") (pintype "passive"))
    )
    (net (code "106") (name "Net-(SR2-Q7S)") (class "Default")
      (node (ref "SR2") (pin "9") (pinfunction "Q7S_9") (pintype "passive"))
      (node (ref "SR3") (pin "14") (pinfunction "DS_14") (pintype "passive"))
    )
    (net (code "107") (name "unconnected-(P1-Pad25)") (class "Default")
      (node (ref "P1") (pin "25") (pinfunction "25_25") (pintype "passive"))
    )
    (net (code "108") (name "unconnected-(P1-Pad26)") (class "Default")
      (node (ref "P1") (pin "26") (pinfunction "26_26") (pintype "passive"))
    )
    (net (code "109") (name "unconnected-(P5-Pad9)") (class "Default")
      (node (ref "P5") (pin "9") (pinfunction "9_9") (pintype "passive"))
    )
    (net (code "110") (name "unconnected-(P5-Pad10)") (class "Default")
      (node (ref "P5") (pin "10") (pinfunction "10_10") (pintype "passive"))
    )
  )
)
